# SRAM_MODULE_1_0.net
KiCad netlist of a schematic drawn in EAGLE
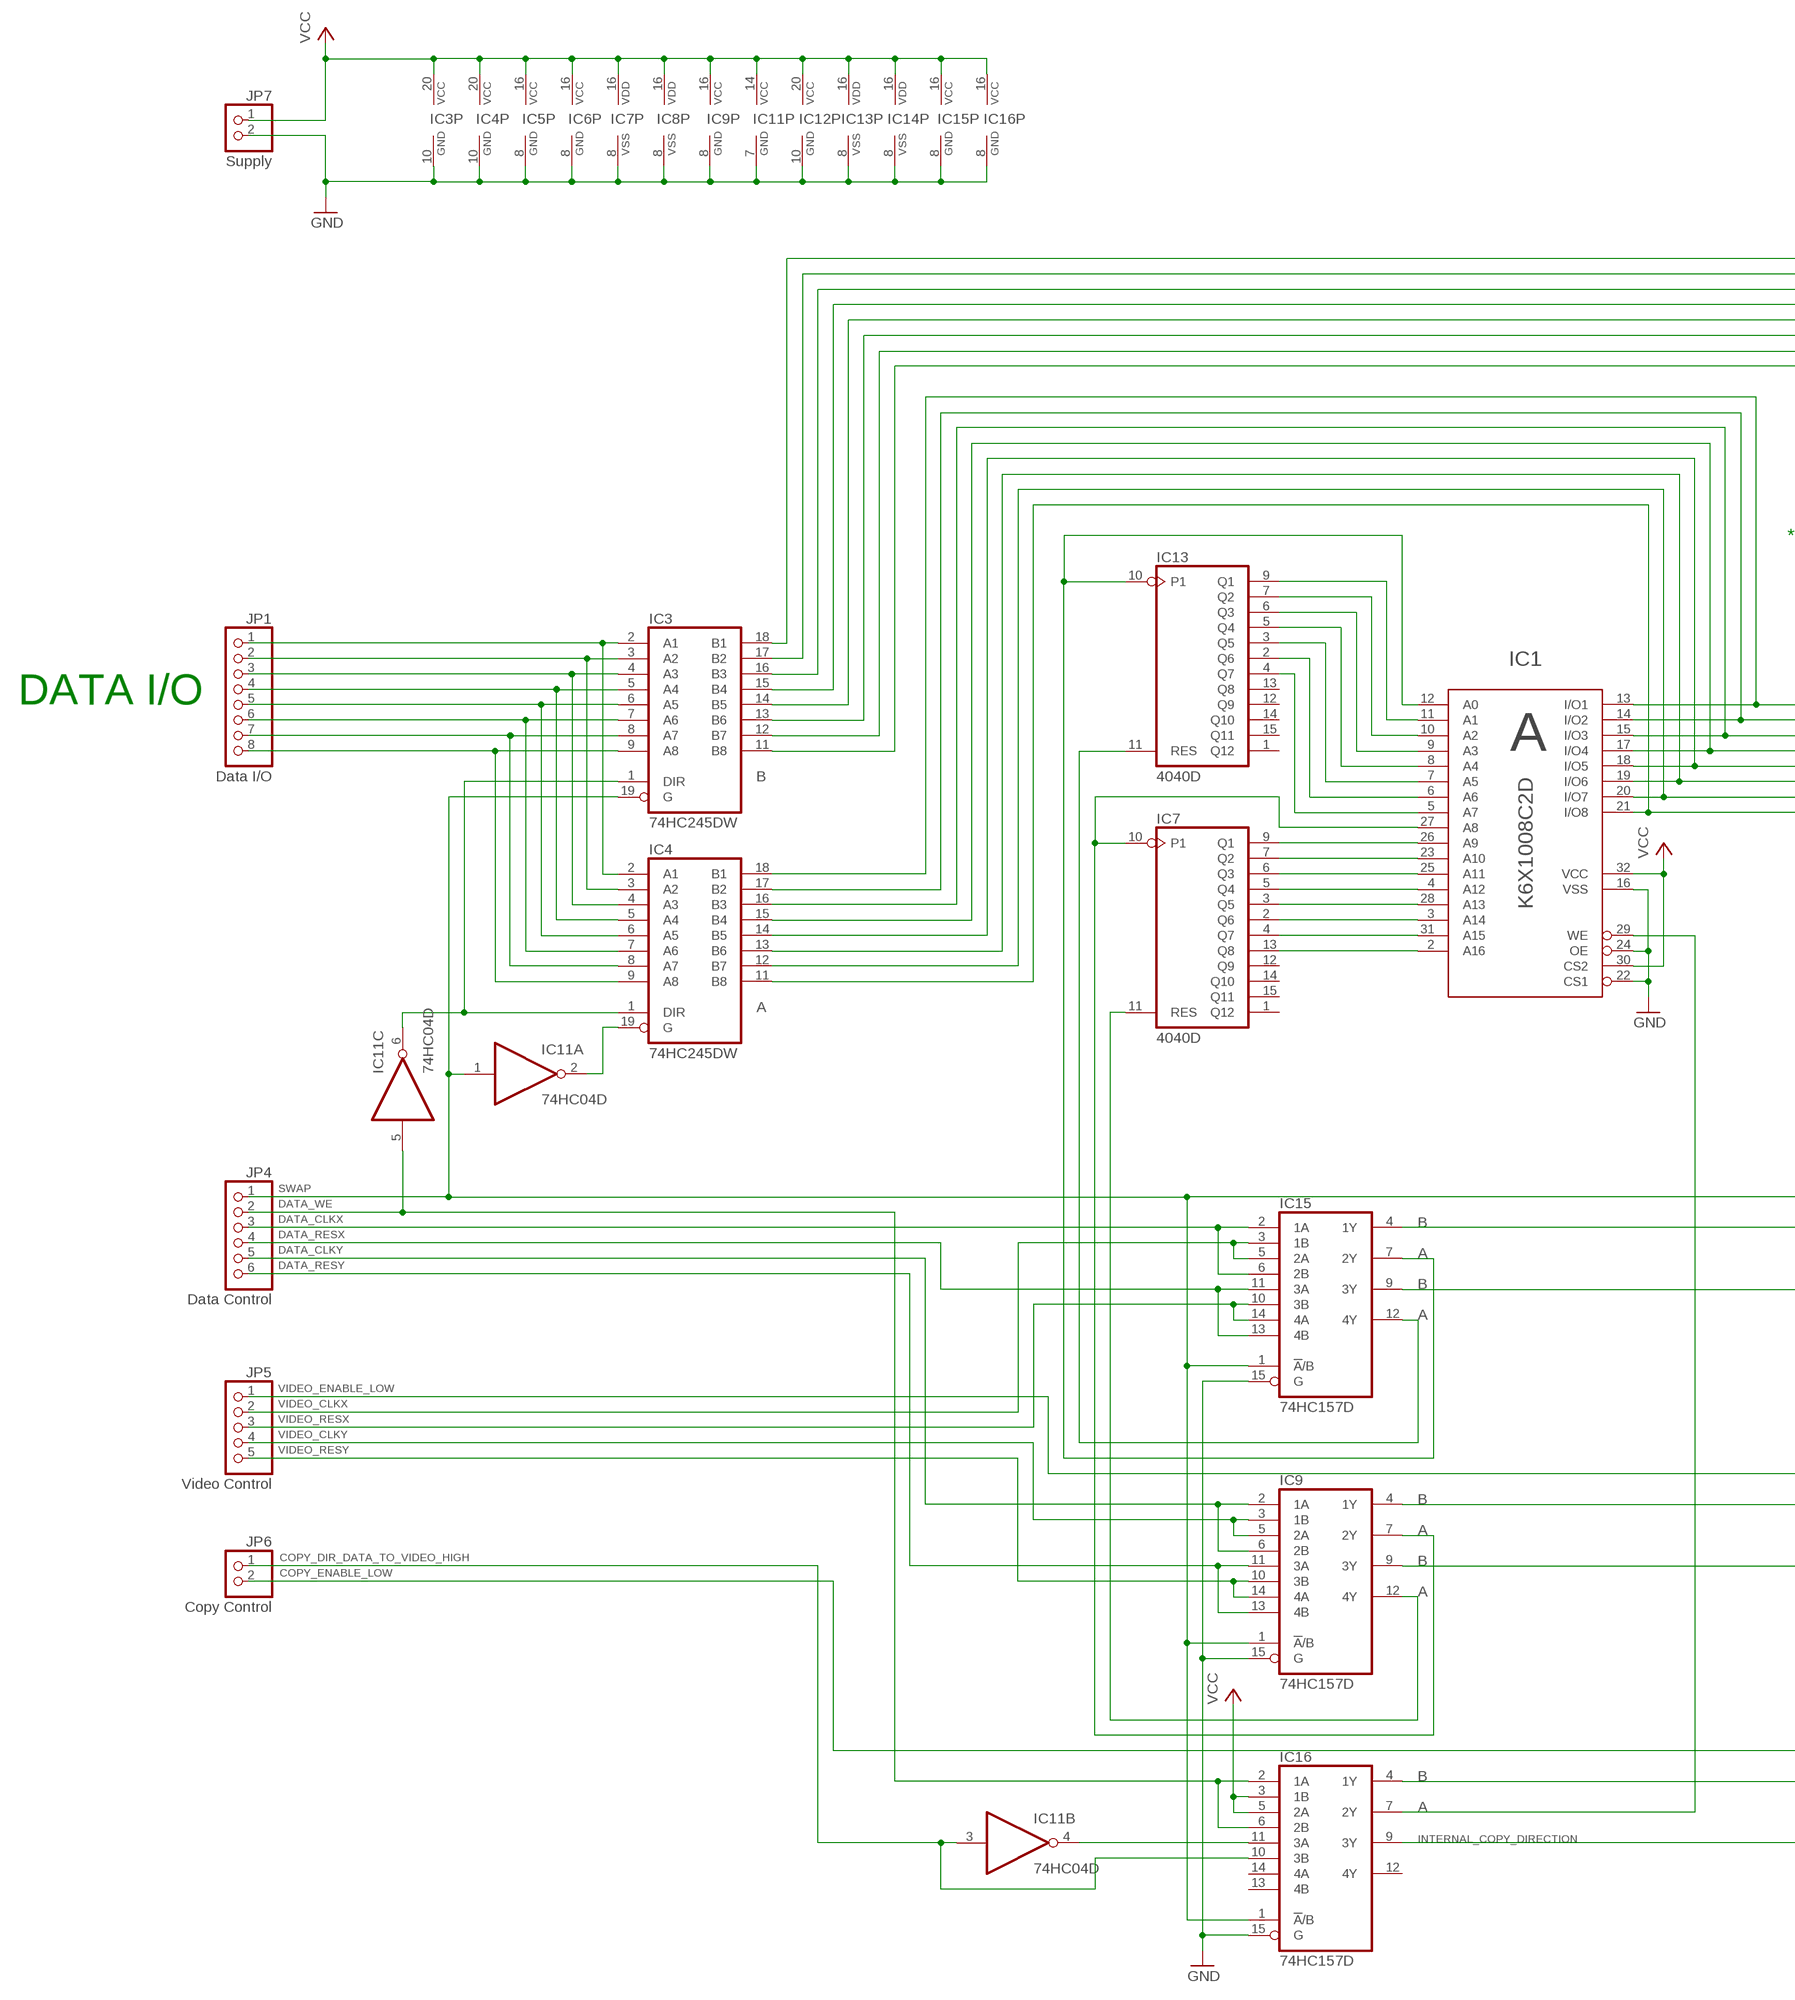
[diagram p0: schematic, sheet 1, part 1 of 2]
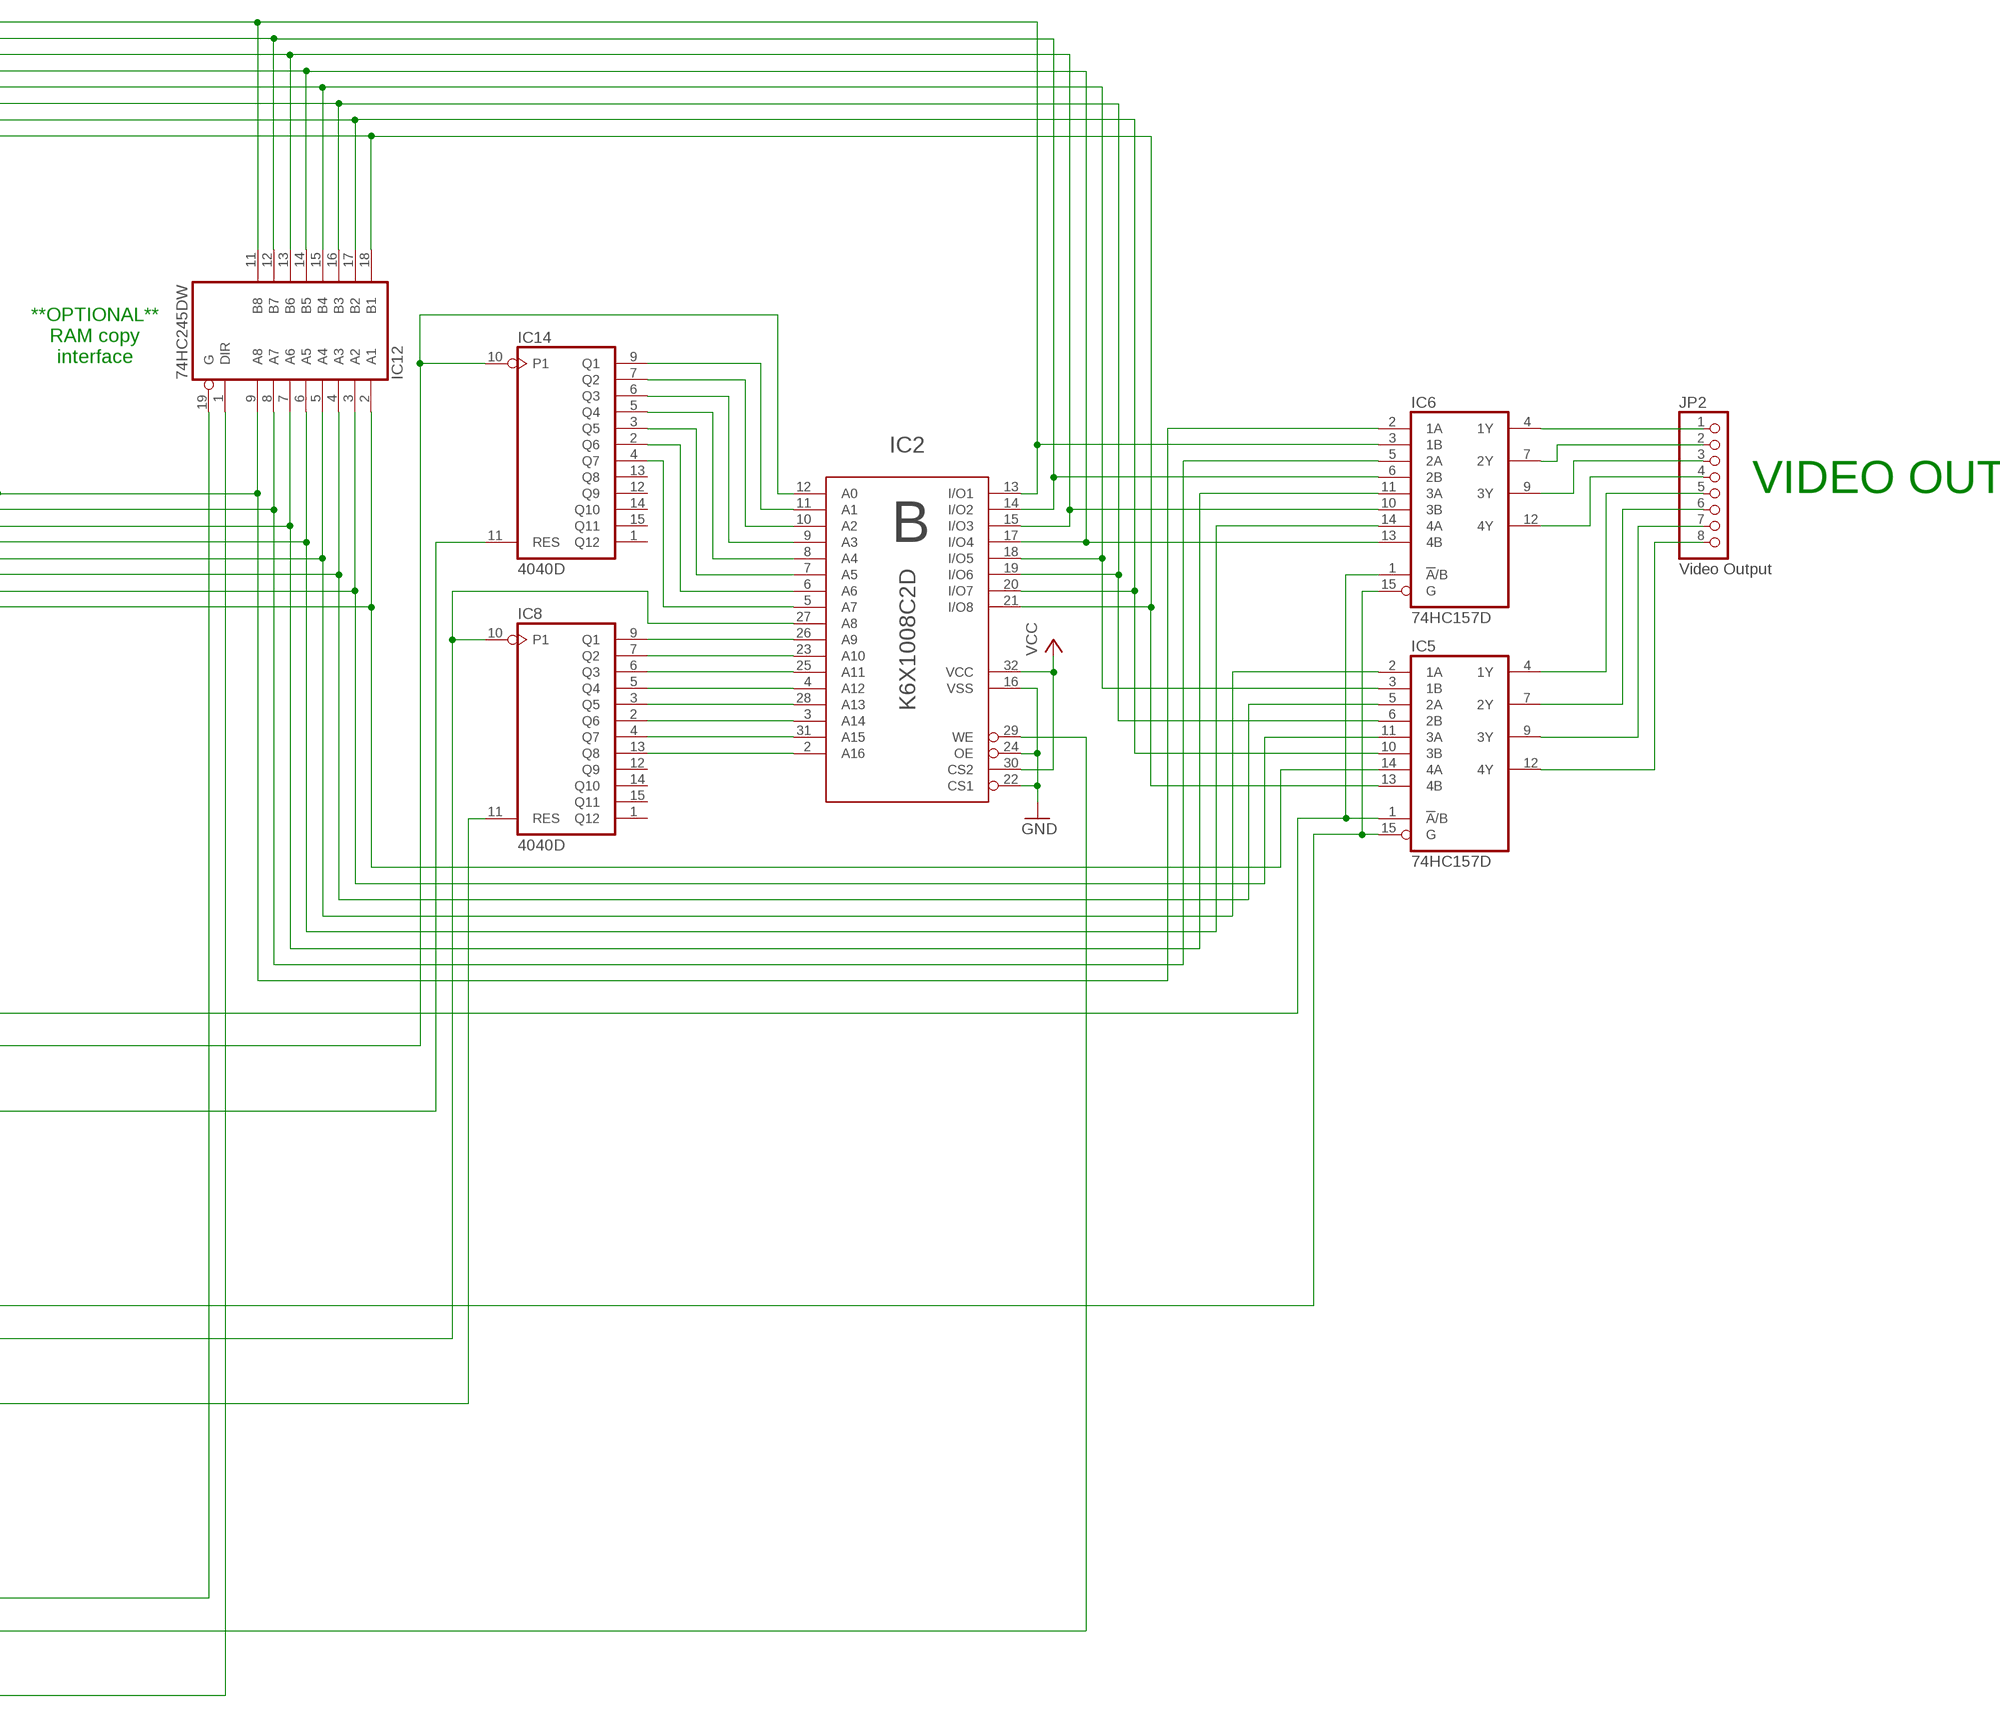
[diagram p1: schematic, sheet 1, part 2 of 2]

(export (version "E")
  (design (tool "Eeschema 10.0.6"))
  (components
    (comp (ref "IC1")
      (value "K6X1008C2D")
      (footprint "eagle-import:SOP32-5")
      (libsource (lib "eagle-import") (part "K6X1008C2D"))
    )
    (comp (ref "IC2")
      (value "K6X1008C2D")
      (footprint "eagle-import:SOP32-5")
      (libsource (lib "eagle-import") (part "K6X1008C2D"))
    )
    (comp (ref "IC3")
      (value "74HC245DW")
      (footprint "eagle-import:SO20W")
      (libsource (lib "eagle-import") (part "74245DWHC"))
    )
    (comp (ref "IC4")
      (value "74HC245DW")
      (footprint "eagle-import:SO20W")
      (libsource (lib "eagle-import") (part "74245DWHC"))
    )
    (comp (ref "IC5")
      (value "74HC157D")
      (footprint "eagle-import:SO16")
      (libsource (lib "eagle-import") (part "74157DHC"))
    )
    (comp (ref "IC6")
      (value "74HC157D")
      (footprint "eagle-import:SO16")
      (libsource (lib "eagle-import") (part "74157DHC"))
    )
    (comp (ref "IC7")
      (value "4040D")
      (footprint "eagle-import:SO16")
      (libsource (lib "eagle-import") (part "4040D"))
    )
    (comp (ref "IC8")
      (value "4040D")
      (footprint "eagle-import:SO16")
      (libsource (lib "eagle-import") (part "4040D"))
    )
    (comp (ref "IC9")
      (value "74HC157D")
      (footprint "eagle-import:SO16")
      (libsource (lib "eagle-import") (part "74157DHC"))
    )
    (comp (ref "IC11")
      (value "74HC04D")
      (footprint "eagle-import:SO14")
      (libsource (lib "eagle-import") (part "7404DHC"))
    )
    (comp (ref "IC12")
      (value "74HC245DW")
      (footprint "eagle-import:SO20W")
      (libsource (lib "eagle-import") (part "74245DWHC"))
    )
    (comp (ref "IC13")
      (value "4040D")
      (footprint "eagle-import:SO16")
      (libsource (lib "eagle-import") (part "4040D"))
    )
    (comp (ref "IC14")
      (value "4040D")
      (footprint "eagle-import:SO16")
      (libsource (lib "eagle-import") (part "4040D"))
    )
    (comp (ref "IC15")
      (value "74HC157D")
      (footprint "eagle-import:SO16")
      (libsource (lib "eagle-import") (part "74157DHC"))
    )
    (comp (ref "IC16")
      (value "74HC157D")
      (footprint "eagle-import:SO16")
      (libsource (lib "eagle-import") (part "74157DHC"))
    )
    (comp (ref "JP1")
      (value "Data I/O")
      (footprint "eagle-import:1X08")
      (libsource (lib "eagle-import") (part "PINHD-1X8"))
    )
    (comp (ref "JP2")
      (value "Video Output")
      (footprint "eagle-import:1X08")
      (libsource (lib "eagle-import") (part "PINHD-1X8"))
    )
    (comp (ref "JP4")
      (value "Data Control")
      (footprint "eagle-import:1X06")
      (libsource (lib "eagle-import") (part "PINHD-1X6"))
    )
    (comp (ref "JP5")
      (value "Video Control")
      (footprint "eagle-import:1X05")
      (libsource (lib "eagle-import") (part "PINHD-1X5"))
    )
    (comp (ref "JP6")
      (value "Copy Control")
      (footprint "eagle-import:1X02")
      (libsource (lib "eagle-import") (part "PINHD-1X2"))
    )
    (comp (ref "JP7")
      (value "Supply")
      (footprint "eagle-import:1X02")
      (libsource (lib "eagle-import") (part "PINHD-1X2"))
    )
  )
  (nets
    (net (code "1") (name "/COPY_DIR_DATA_TO_VIDEO_HIGH") (class "Default")
      (node (ref "IC11") (pin "3") (pinfunction "I_3") (pintype "input"))
      (node (ref "IC16") (pin "10") (pinfunction "3B_10") (pintype "input"))
      (node (ref "JP6") (pin "1") (pinfunction "1_1") (pintype "passive"))
    )
    (net (code "2") (name "/COPY_ENABLE_LOW") (class "Default")
      (node (ref "IC12") (pin "19") (pinfunction "G_19") (pintype "input"))
      (node (ref "JP6") (pin "2") (pinfunction "2_2") (pintype "passive"))
    )
    (net (code "3") (name "/DATA_CLKX") (class "Default")
      (node (ref "IC15") (pin "2") (pinfunction "1A_2") (pintype "input"))
      (node (ref "IC15") (pin "6") (pinfunction "2B_6") (pintype "input"))
      (node (ref "JP4") (pin "3") (pinfunction "3_3") (pintype "passive"))
    )
    (net (code "4") (name "/DATA_CLKY") (class "Default")
      (node (ref "IC9") (pin "2") (pinfunction "1A_2") (pintype "input"))
      (node (ref "IC9") (pin "6") (pinfunction "2B_6") (pintype "input"))
      (node (ref "JP4") (pin "5") (pinfunction "5_5") (pintype "passive"))
    )
    (net (code "5") (name "/DATA_RESX") (class "Default")
      (node (ref "IC15") (pin "11") (pinfunction "3A_11") (pintype "input"))
      (node (ref "IC15") (pin "13") (pinfunction "4B_13") (pintype "input"))
      (node (ref "JP4") (pin "4") (pinfunction "4_4") (pintype "passive"))
    )
    (net (code "6") (name "/DATA_RESY") (class "Default")
      (node (ref "IC9") (pin "11") (pinfunction "3A_11") (pintype "input"))
      (node (ref "IC9") (pin "13") (pinfunction "4B_13") (pintype "input"))
      (node (ref "JP4") (pin "6") (pinfunction "6_6") (pintype "passive"))
    )
    (net (code "7") (name "/DATA_WE") (class "Default")
      (node (ref "IC11") (pin "5") (pinfunction "I_5") (pintype "input"))
      (node (ref "IC16") (pin "2") (pinfunction "1A_2") (pintype "input"))
      (node (ref "IC16") (pin "6") (pinfunction "2B_6") (pintype "input"))
      (node (ref "JP4") (pin "2") (pinfunction "2_2") (pintype "passive"))
    )
    (net (code "8") (name "/INTERNAL_COPY_DIRECTION") (class "Default")
      (node (ref "IC12") (pin "1") (pinfunction "DIR_1") (pintype "input"))
      (node (ref "IC16") (pin "9") (pinfunction "3Y_9") (pintype "output"))
    )
    (net (code "9") (name "/SWAP") (class "Default")
      (node (ref "IC11") (pin "1") (pinfunction "I_1") (pintype "input"))
      (node (ref "IC15") (pin "1") (pinfunction "~{A}/B_1") (pintype "input"))
      (node (ref "IC16") (pin "1") (pinfunction "~{A}/B_1") (pintype "input"))
      (node (ref "IC3") (pin "19") (pinfunction "G_19") (pintype "input"))
      (node (ref "IC5") (pin "1") (pinfunction "~{A}/B_1") (pintype "input"))
      (node (ref "IC6") (pin "1") (pinfunction "~{A}/B_1") (pintype "input"))
      (node (ref "IC9") (pin "1") (pinfunction "~{A}/B_1") (pintype "input"))
      (node (ref "JP4") (pin "1") (pinfunction "1_1") (pintype "passive"))
    )
    (net (code "10") (name "/VIDEO_CLKX") (class "Default")
      (node (ref "IC15") (pin "3") (pinfunction "1B_3") (pintype "input"))
      (node (ref "IC15") (pin "5") (pinfunction "2A_5") (pintype "input"))
      (node (ref "JP5") (pin "2") (pinfunction "2_2") (pintype "passive"))
    )
    (net (code "11") (name "/VIDEO_CLKY") (class "Default")
      (node (ref "IC9") (pin "3") (pinfunction "1B_3") (pintype "input"))
      (node (ref "IC9") (pin "5") (pinfunction "2A_5") (pintype "input"))
      (node (ref "JP5") (pin "4") (pinfunction "4_4") (pintype "passive"))
    )
    (net (code "12") (name "/VIDEO_ENABLE_LOW") (class "Default")
      (node (ref "IC5") (pin "15") (pinfunction "G_15") (pintype "input"))
      (node (ref "IC6") (pin "15") (pinfunction "G_15") (pintype "input"))
      (node (ref "JP5") (pin "1") (pinfunction "1_1") (pintype "passive"))
    )
    (net (code "13") (name "/VIDEO_RESX") (class "Default")
      (node (ref "IC15") (pin "10") (pinfunction "3B_10") (pintype "input"))
      (node (ref "IC15") (pin "14") (pinfunction "4A_14") (pintype "input"))
      (node (ref "JP5") (pin "3") (pinfunction "3_3") (pintype "passive"))
    )
    (net (code "14") (name "/VIDEO_RESY") (class "Default")
      (node (ref "IC9") (pin "10") (pinfunction "3B_10") (pintype "input"))
      (node (ref "IC9") (pin "14") (pinfunction "4A_14") (pintype "input"))
      (node (ref "JP5") (pin "5") (pinfunction "5_5") (pintype "passive"))
    )
    (net (code "15") (name "GND") (class "Default")
      (node (ref "IC1") (pin "16") (pinfunction "VSS_16") (pintype "power_in"))
      (node (ref "IC1") (pin "22") (pinfunction "CS1_22") (pintype "input"))
      (node (ref "IC1") (pin "24") (pinfunction "OE_24") (pintype "input"))
      (node (ref "IC11") (pin "7") (pinfunction "GND_7") (pintype "power_in"))
      (node (ref "IC12") (pin "10") (pinfunction "GND_10") (pintype "power_in"))
      (node (ref "IC13") (pin "8") (pinfunction "VSS_8") (pintype "power_in"))
      (node (ref "IC14") (pin "8") (pinfunction "VSS_8") (pintype "power_in"))
      (node (ref "IC15") (pin "15") (pinfunction "G_15") (pintype "input"))
      (node (ref "IC15") (pin "8") (pinfunction "GND_8") (pintype "power_in"))
      (node (ref "IC16") (pin "15") (pinfunction "G_15") (pintype "input"))
      (node (ref "IC16") (pin "8") (pinfunction "GND_8") (pintype "power_in"))
      (node (ref "IC2") (pin "16") (pinfunction "VSS_16") (pintype "power_in"))
      (node (ref "IC2") (pin "22") (pinfunction "CS1_22") (pintype "input"))
      (node (ref "IC2") (pin "24") (pinfunction "OE_24") (pintype "input"))
      (node (ref "IC3") (pin "10") (pinfunction "GND_10") (pintype "power_in"))
      (node (ref "IC4") (pin "10") (pinfunction "GND_10") (pintype "power_in"))
      (node (ref "IC5") (pin "8") (pinfunction "GND_8") (pintype "power_in"))
      (node (ref "IC6") (pin "8") (pinfunction "GND_8") (pintype "power_in"))
      (node (ref "IC7") (pin "8") (pinfunction "VSS_8") (pintype "power_in"))
      (node (ref "IC8") (pin "8") (pinfunction "VSS_8") (pintype "power_in"))
      (node (ref "IC9") (pin "15") (pinfunction "G_15") (pintype "input"))
      (node (ref "IC9") (pin "8") (pinfunction "GND_8") (pintype "power_in"))
      (node (ref "JP7") (pin "2") (pinfunction "2_2") (pintype "passive"))
    )
    (net (code "16") (name "Net-(IC1-A0)") (class "Default")
      (node (ref "IC1") (pin "12") (pinfunction "A0_12") (pintype "input"))
      (node (ref "IC13") (pin "10") (pinfunction "P1_10") (pintype "input"))
      (node (ref "IC15") (pin "7") (pinfunction "2Y_7") (pintype "output"))
    )
    (net (code "17") (name "Net-(IC1-A1)") (class "Default")
      (node (ref "IC1") (pin "11") (pinfunction "A1_11") (pintype "input"))
      (node (ref "IC13") (pin "9") (pinfunction "Q1_9") (pintype "output"))
    )
    (net (code "18") (name "Net-(IC1-A2)") (class "Default")
      (node (ref "IC1") (pin "10") (pinfunction "A2_10") (pintype "input"))
      (node (ref "IC13") (pin "7") (pinfunction "Q2_7") (pintype "output"))
    )
    (net (code "19") (name "Net-(IC1-A3)") (class "Default")
      (node (ref "IC1") (pin "9") (pinfunction "A3_9") (pintype "input"))
      (node (ref "IC13") (pin "6") (pinfunction "Q3_6") (pintype "output"))
    )
    (net (code "20") (name "Net-(IC1-A4)") (class "Default")
      (node (ref "IC1") (pin "8") (pinfunction "A4_8") (pintype "input"))
      (node (ref "IC13") (pin "5") (pinfunction "Q4_5") (pintype "output"))
    )
    (net (code "21") (name "Net-(IC1-A5)") (class "Default")
      (node (ref "IC1") (pin "7") (pinfunction "A5_7") (pintype "input"))
      (node (ref "IC13") (pin "3") (pinfunction "Q5_3") (pintype "output"))
    )
    (net (code "22") (name "Net-(IC1-A6)") (class "Default")
      (node (ref "IC1") (pin "6") (pinfunction "A6_6") (pintype "input"))
      (node (ref "IC13") (pin "2") (pinfunction "Q6_2") (pintype "output"))
    )
    (net (code "23") (name "Net-(IC1-A7)") (class "Default")
      (node (ref "IC1") (pin "5") (pinfunction "A7_5") (pintype "input"))
      (node (ref "IC13") (pin "4") (pinfunction "Q7_4") (pintype "output"))
    )
    (net (code "24") (name "Net-(IC1-A8)") (class "Default")
      (node (ref "IC1") (pin "27") (pinfunction "A8_27") (pintype "input"))
      (node (ref "IC7") (pin "10") (pinfunction "P1_10") (pintype "input"))
      (node (ref "IC9") (pin "7") (pinfunction "2Y_7") (pintype "output"))
    )
    (net (code "25") (name "Net-(IC1-A9)") (class "Default")
      (node (ref "IC1") (pin "26") (pinfunction "A9_26") (pintype "input"))
      (node (ref "IC7") (pin "9") (pinfunction "Q1_9") (pintype "output"))
    )
    (net (code "26") (name "Net-(IC1-A10)") (class "Default")
      (node (ref "IC1") (pin "23") (pinfunction "A10_23") (pintype "input"))
      (node (ref "IC7") (pin "7") (pinfunction "Q2_7") (pintype "output"))
    )
    (net (code "27") (name "Net-(IC1-A11)") (class "Default")
      (node (ref "IC1") (pin "25") (pinfunction "A11_25") (pintype "input"))
      (node (ref "IC7") (pin "6") (pinfunction "Q3_6") (pintype "output"))
    )
    (net (code "28") (name "Net-(IC1-A12)") (class "Default")
      (node (ref "IC1") (pin "4") (pinfunction "A12_4") (pintype "input"))
      (node (ref "IC7") (pin "5") (pinfunction "Q4_5") (pintype "output"))
    )
    (net (code "29") (name "Net-(IC1-A13)") (class "Default")
      (node (ref "IC1") (pin "28") (pinfunction "A13_28") (pintype "input"))
      (node (ref "IC7") (pin "3") (pinfunction "Q5_3") (pintype "output"))
    )
    (net (code "30") (name "Net-(IC1-A14)") (class "Default")
      (node (ref "IC1") (pin "3") (pinfunction "A14_3") (pintype "input"))
      (node (ref "IC7") (pin "2") (pinfunction "Q6_2") (pintype "output"))
    )
    (net (code "31") (name "Net-(IC1-A15)") (class "Default")
      (node (ref "IC1") (pin "31") (pinfunction "A15_31") (pintype "input"))
      (node (ref "IC7") (pin "4") (pinfunction "Q7_4") (pintype "output"))
    )
    (net (code "32") (name "Net-(IC1-A16)") (class "Default")
      (node (ref "IC1") (pin "2") (pinfunction "A16_2") (pintype "input"))
      (node (ref "IC7") (pin "13") (pinfunction "Q8_13") (pintype "output"))
    )
    (net (code "33") (name "Net-(IC1-I{slash}O1)") (class "Default")
      (node (ref "IC1") (pin "13") (pinfunction "I/O1_13") (pintype "bidirectional"))
      (node (ref "IC12") (pin "9") (pinfunction "A8_9") (pintype "bidirectional"))
      (node (ref "IC4") (pin "18") (pinfunction "B1_18") (pintype "bidirectional"))
      (node (ref "IC6") (pin "2") (pinfunction "1A_2") (pintype "input"))
    )
    (net (code "34") (name "Net-(IC1-I{slash}O2)") (class "Default")
      (node (ref "IC1") (pin "14") (pinfunction "I/O2_14") (pintype "bidirectional"))
      (node (ref "IC12") (pin "8") (pinfunction "A7_8") (pintype "bidirectional"))
      (node (ref "IC4") (pin "17") (pinfunction "B2_17") (pintype "bidirectional"))
      (node (ref "IC6") (pin "5") (pinfunction "2A_5") (pintype "input"))
    )
    (net (code "35") (name "Net-(IC1-I{slash}O3)") (class "Default")
      (node (ref "IC1") (pin "15") (pinfunction "I/O3_15") (pintype "bidirectional"))
      (node (ref "IC12") (pin "7") (pinfunction "A6_7") (pintype "bidirectional"))
      (node (ref "IC4") (pin "16") (pinfunction "B3_16") (pintype "bidirectional"))
      (node (ref "IC6") (pin "11") (pinfunction "3A_11") (pintype "input"))
    )
    (net (code "36") (name "Net-(IC1-I{slash}O4)") (class "Default")
      (node (ref "IC1") (pin "17") (pinfunction "I/O4_17") (pintype "bidirectional"))
      (node (ref "IC12") (pin "6") (pinfunction "A5_6") (pintype "bidirectional"))
      (node (ref "IC4") (pin "15") (pinfunction "B4_15") (pintype "bidirectional"))
      (node (ref "IC6") (pin "14") (pinfunction "4A_14") (pintype "input"))
    )
    (net (code "37") (name "Net-(IC1-I{slash}O5)") (class "Default")
      (node (ref "IC1") (pin "18") (pinfunction "I/O5_18") (pintype "bidirectional"))
      (node (ref "IC12") (pin "5") (pinfunction "A4_5") (pintype "bidirectional"))
      (node (ref "IC4") (pin "14") (pinfunction "B5_14") (pintype "bidirectional"))
      (node (ref "IC5") (pin "2") (pinfunction "1A_2") (pintype "input"))
    )
    (net (code "38") (name "Net-(IC1-I{slash}O6)") (class "Default")
      (node (ref "IC1") (pin "19") (pinfunction "I/O6_19") (pintype "bidirectional"))
      (node (ref "IC12") (pin "4") (pinfunction "A3_4") (pintype "bidirectional"))
      (node (ref "IC4") (pin "13") (pinfunction "B6_13") (pintype "bidirectional"))
      (node (ref "IC5") (pin "5") (pinfunction "2A_5") (pintype "input"))
    )
    (net (code "39") (name "Net-(IC1-I{slash}O7)") (class "Default")
      (node (ref "IC1") (pin "20") (pinfunction "I/O7_20") (pintype "bidirectional"))
      (node (ref "IC12") (pin "3") (pinfunction "A2_3") (pintype "bidirectional"))
      (node (ref "IC4") (pin "12") (pinfunction "B7_12") (pintype "bidirectional"))
      (node (ref "IC5") (pin "11") (pinfunction "3A_11") (pintype "input"))
    )
    (net (code "40") (name "Net-(IC1-I{slash}O8)") (class "Default")
      (node (ref "IC1") (pin "21") (pinfunction "I/O8_21") (pintype "bidirectional"))
      (node (ref "IC12") (pin "2") (pinfunction "A1_2") (pintype "bidirectional"))
      (node (ref "IC4") (pin "11") (pinfunction "B8_11") (pintype "bidirectional"))
      (node (ref "IC5") (pin "14") (pinfunction "4A_14") (pintype "input"))
    )
    (net (code "41") (name "Net-(IC1-WE)") (class "Default")
      (node (ref "IC1") (pin "29") (pinfunction "WE_29") (pintype "input"))
      (node (ref "IC16") (pin "7") (pinfunction "2Y_7") (pintype "output"))
    )
    (net (code "42") (name "Net-(IC2-A8)") (class "Default")
      (node (ref "IC2") (pin "27") (pinfunction "A8_27") (pintype "input"))
      (node (ref "IC8") (pin "10") (pinfunction "P1_10") (pintype "input"))
      (node (ref "IC9") (pin "4") (pinfunction "1Y_4") (pintype "output"))
    )
    (net (code "43") (name "Net-(IC2-A9)") (class "Default")
      (node (ref "IC2") (pin "26") (pinfunction "A9_26") (pintype "input"))
      (node (ref "IC8") (pin "9") (pinfunction "Q1_9") (pintype "output"))
    )
    (net (code "44") (name "Net-(IC2-A10)") (class "Default")
      (node (ref "IC2") (pin "23") (pinfunction "A10_23") (pintype "input"))
      (node (ref "IC8") (pin "7") (pinfunction "Q2_7") (pintype "output"))
    )
    (net (code "45") (name "Net-(IC2-A11)") (class "Default")
      (node (ref "IC2") (pin "25") (pinfunction "A11_25") (pintype "input"))
      (node (ref "IC8") (pin "6") (pinfunction "Q3_6") (pintype "output"))
    )
    (net (code "46") (name "Net-(IC2-A12)") (class "Default")
      (node (ref "IC2") (pin "4") (pinfunction "A12_4") (pintype "input"))
      (node (ref "IC8") (pin "5") (pinfunction "Q4_5") (pintype "output"))
    )
    (net (code "47") (name "Net-(IC2-A13)") (class "Default")
      (node (ref "IC2") (pin "28") (pinfunction "A13_28") (pintype "input"))
      (node (ref "IC8") (pin "3") (pinfunction "Q5_3") (pintype "output"))
    )
    (net (code "48") (name "Net-(IC2-A14)") (class "Default")
      (node (ref "IC2") (pin "3") (pinfunction "A14_3") (pintype "input"))
      (node (ref "IC8") (pin "2") (pinfunction "Q6_2") (pintype "output"))
    )
    (net (code "49") (name "Net-(IC2-A15)") (class "Default")
      (node (ref "IC2") (pin "31") (pinfunction "A15_31") (pintype "input"))
      (node (ref "IC8") (pin "4") (pinfunction "Q7_4") (pintype "output"))
    )
    (net (code "50") (name "Net-(IC2-A16)") (class "Default")
      (node (ref "IC2") (pin "2") (pinfunction "A16_2") (pintype "input"))
      (node (ref "IC8") (pin "13") (pinfunction "Q8_13") (pintype "output"))
    )
    (net (code "51") (name "Net-(IC3A-A1)") (class "Default")
      (node (ref "IC3") (pin "2") (pinfunction "A1_2") (pintype "bidirectional"))
      (node (ref "IC4") (pin "2") (pinfunction "A1_2") (pintype "bidirectional"))
      (node (ref "JP1") (pin "1") (pinfunction "1_1") (pintype "passive"))
    )
    (net (code "52") (name "Net-(IC3A-A2)") (class "Default")
      (node (ref "IC3") (pin "3") (pinfunction "A2_3") (pintype "bidirectional"))
      (node (ref "IC4") (pin "3") (pinfunction "A2_3") (pintype "bidirectional"))
      (node (ref "JP1") (pin "2") (pinfunction "2_2") (pintype "passive"))
    )
    (net (code "53") (name "Net-(IC3A-A3)") (class "Default")
      (node (ref "IC3") (pin "4") (pinfunction "A3_4") (pintype "bidirectional"))
      (node (ref "IC4") (pin "4") (pinfunction "A3_4") (pintype "bidirectional"))
      (node (ref "JP1") (pin "3") (pinfunction "3_3") (pintype "passive"))
    )
    (net (code "54") (name "Net-(IC3A-A4)") (class "Default")
      (node (ref "IC3") (pin "5") (pinfunction "A4_5") (pintype "bidirectional"))
      (node (ref "IC4") (pin "5") (pinfunction "A4_5") (pintype "bidirectional"))
      (node (ref "JP1") (pin "4") (pinfunction "4_4") (pintype "passive"))
    )
    (net (code "55") (name "Net-(IC3A-A5)") (class "Default")
      (node (ref "IC3") (pin "6") (pinfunction "A5_6") (pintype "bidirectional"))
      (node (ref "IC4") (pin "6") (pinfunction "A5_6") (pintype "bidirectional"))
      (node (ref "JP1") (pin "5") (pinfunction "5_5") (pintype "passive"))
    )
    (net (code "56") (name "Net-(IC3A-A6)") (class "Default")
      (node (ref "IC3") (pin "7") (pinfunction "A6_7") (pintype "bidirectional"))
      (node (ref "IC4") (pin "7") (pinfunction "A6_7") (pintype "bidirectional"))
      (node (ref "JP1") (pin "6") (pinfunction "6_6") (pintype "passive"))
    )
    (net (code "57") (name "Net-(IC3A-A7)") (class "Default")
      (node (ref "IC3") (pin "8") (pinfunction "A7_8") (pintype "bidirectional"))
      (node (ref "IC4") (pin "8") (pinfunction "A7_8") (pintype "bidirectional"))
      (node (ref "JP1") (pin "7") (pinfunction "7_7") (pintype "passive"))
    )
    (net (code "58") (name "Net-(IC3A-A8)") (class "Default")
      (node (ref "IC3") (pin "9") (pinfunction "A8_9") (pintype "bidirectional"))
      (node (ref "IC4") (pin "9") (pinfunction "A8_9") (pintype "bidirectional"))
      (node (ref "JP1") (pin "8") (pinfunction "8_8") (pintype "passive"))
    )
    (net (code "59") (name "Net-(IC5A-1Y)") (class "Default")
      (node (ref "IC5") (pin "4") (pinfunction "1Y_4") (pintype "output"))
      (node (ref "JP2") (pin "5") (pinfunction "5_5") (pintype "passive"))
    )
    (net (code "60") (name "Net-(IC5A-2Y)") (class "Default")
      (node (ref "IC5") (pin "7") (pinfunction "2Y_7") (pintype "output"))
      (node (ref "JP2") (pin "6") (pinfunction "6_6") (pintype "passive"))
    )
    (net (code "61") (name "Net-(IC5A-3Y)") (class "Default")
      (node (ref "IC5") (pin "9") (pinfunction "3Y_9") (pintype "output"))
      (node (ref "JP2") (pin "7") (pinfunction "7_7") (pintype "passive"))
    )
    (net (code "62") (name "Net-(IC5A-4Y)") (class "Default")
      (node (ref "IC5") (pin "12") (pinfunction "4Y_12") (pintype "output"))
      (node (ref "JP2") (pin "8") (pinfunction "8_8") (pintype "passive"))
    )
    (net (code "63") (name "Net-(IC6A-1Y)") (class "Default")
      (node (ref "IC6") (pin "4") (pinfunction "1Y_4") (pintype "output"))
      (node (ref "JP2") (pin "1") (pinfunction "1_1") (pintype "passive"))
    )
    (net (code "64") (name "Net-(IC6A-2Y)") (class "Default")
      (node (ref "IC6") (pin "7") (pinfunction "2Y_7") (pintype "output"))
      (node (ref "JP2") (pin "2") (pinfunction "2_2") (pintype "passive"))
    )
    (net (code "65") (name "Net-(IC6A-3Y)") (class "Default")
      (node (ref "IC6") (pin "9") (pinfunction "3Y_9") (pintype "output"))
      (node (ref "JP2") (pin "3") (pinfunction "3_3") (pintype "passive"))
    )
    (net (code "66") (name "Net-(IC6A-4Y)") (class "Default")
      (node (ref "IC6") (pin "12") (pinfunction "4Y_12") (pintype "output"))
      (node (ref "JP2") (pin "4") (pinfunction "4_4") (pintype "passive"))
    )
    (net (code "67") (name "Net-(IC7A-RES)") (class "Default")
      (node (ref "IC7") (pin "11") (pinfunction "RES_11") (pintype "input"))
      (node (ref "IC9") (pin "12") (pinfunction "4Y_12") (pintype "output"))
    )
    (net (code "68") (name "Net-(IC8A-RES)") (class "Default")
      (node (ref "IC8") (pin "11") (pinfunction "RES_11") (pintype "input"))
      (node (ref "IC9") (pin "9") (pinfunction "3Y_9") (pintype "output"))
    )
    (net (code "69") (name "Net-(IC11A-O)") (class "Default")
      (node (ref "IC11") (pin "2") (pinfunction "O_2") (pintype "output"))
      (node (ref "IC4") (pin "19") (pinfunction "G_19") (pintype "input"))
    )
    (net (code "70") (name "Net-(IC11B-O)") (class "Default")
      (node (ref "IC11") (pin "4") (pinfunction "O_4") (pintype "output"))
      (node (ref "IC16") (pin "11") (pinfunction "3A_11") (pintype "input"))
    )
    (net (code "71") (name "Net-(IC11C-O)") (class "Default")
      (node (ref "IC11") (pin "6") (pinfunction "O_6") (pintype "output"))
      (node (ref "IC3") (pin "1") (pinfunction "DIR_1") (pintype "input"))
      (node (ref "IC4") (pin "1") (pinfunction "DIR_1") (pintype "input"))
    )
    (net (code "72") (name "Net-(IC12A-B1)") (class "Default")
      (node (ref "IC12") (pin "18") (pinfunction "B1_18") (pintype "bidirectional"))
      (node (ref "IC2") (pin "21") (pinfunction "I/O8_21") (pintype "bidirectional"))
      (node (ref "IC3") (pin "11") (pinfunction "B8_11") (pintype "bidirectional"))
      (node (ref "IC5") (pin "13") (pinfunction "4B_13") (pintype "input"))
    )
    (net (code "73") (name "Net-(IC12A-B2)") (class "Default")
      (node (ref "IC12") (pin "17") (pinfunction "B2_17") (pintype "bidirectional"))
      (node (ref "IC2") (pin "20") (pinfunction "I/O7_20") (pintype "bidirectional"))
      (node (ref "IC3") (pin "12") (pinfunction "B7_12") (pintype "bidirectional"))
      (node (ref "IC5") (pin "10") (pinfunction "3B_10") (pintype "input"))
    )
    (net (code "74") (name "Net-(IC12A-B3)") (class "Default")
      (node (ref "IC12") (pin "16") (pinfunction "B3_16") (pintype "bidirectional"))
      (node (ref "IC2") (pin "19") (pinfunction "I/O6_19") (pintype "bidirectional"))
      (node (ref "IC3") (pin "13") (pinfunction "B6_13") (pintype "bidirectional"))
      (node (ref "IC5") (pin "6") (pinfunction "2B_6") (pintype "input"))
    )
    (net (code "75") (name "Net-(IC12A-B4)") (class "Default")
      (node (ref "IC12") (pin "15") (pinfunction "B4_15") (pintype "bidirectional"))
      (node (ref "IC2") (pin "18") (pinfunction "I/O5_18") (pintype "bidirectional"))
      (node (ref "IC3") (pin "14") (pinfunction "B5_14") (pintype "bidirectional"))
      (node (ref "IC5") (pin "3") (pinfunction "1B_3") (pintype "input"))
    )
    (net (code "76") (name "Net-(IC12A-B5)") (class "Default")
      (node (ref "IC12") (pin "14") (pinfunction "B5_14") (pintype "bidirectional"))
      (node (ref "IC2") (pin "17") (pinfunction "I/O4_17") (pintype "bidirectional"))
      (node (ref "IC3") (pin "15") (pinfunction "B4_15") (pintype "bidirectional"))
      (node (ref "IC6") (pin "13") (pinfunction "4B_13") (pintype "input"))
    )
    (net (code "77") (name "Net-(IC12A-B6)") (class "Default")
      (node (ref "IC12") (pin "13") (pinfunction "B6_13") (pintype "bidirectional"))
      (node (ref "IC2") (pin "15") (pinfunction "I/O3_15") (pintype "bidirectional"))
      (node (ref "IC3") (pin "16") (pinfunction "B3_16") (pintype "bidirectional"))
      (node (ref "IC6") (pin "10") (pinfunction "3B_10") (pintype "input"))
    )
    (net (code "78") (name "Net-(IC12A-B7)") (class "Default")
      (node (ref "IC12") (pin "12") (pinfunction "B7_12") (pintype "bidirectional"))
      (node (ref "IC2") (pin "14") (pinfunction "I/O2_14") (pintype "bidirectional"))
      (node (ref "IC3") (pin "17") (pinfunction "B2_17") (pintype "bidirectional"))
      (node (ref "IC6") (pin "6") (pinfunction "2B_6") (pintype "input"))
    )
    (net (code "79") (name "Net-(IC12A-B8)") (class "Default")
      (node (ref "IC12") (pin "11") (pinfunction "B8_11") (pintype "bidirectional"))
      (node (ref "IC2") (pin "13") (pinfunction "I/O1_13") (pintype "bidirectional"))
      (node (ref "IC3") (pin "18") (pinfunction "B1_18") (pintype "bidirectional"))
      (node (ref "IC6") (pin "3") (pinfunction "1B_3") (pintype "input"))
    )
    (net (code "80") (name "Net-(IC13A-RES)") (class "Default")
      (node (ref "IC13") (pin "11") (pinfunction "RES_11") (pintype "input"))
      (node (ref "IC15") (pin "12") (pinfunction "4Y_12") (pintype "output"))
    )
    (net (code "81") (name "Net-(IC14A-P1)") (class "Default")
      (node (ref "IC14") (pin "10") (pinfunction "P1_10") (pintype "input"))
      (node (ref "IC15") (pin "4") (pinfunction "1Y_4") (pintype "output"))
      (node (ref "IC2") (pin "12") (pinfunction "A0_12") (pintype "input"))
    )
    (net (code "82") (name "Net-(IC14A-Q1)") (class "Default")
      (node (ref "IC14") (pin "9") (pinfunction "Q1_9") (pintype "output"))
      (node (ref "IC2") (pin "11") (pinfunction "A1_11") (pintype "input"))
    )
    (net (code "83") (name "Net-(IC14A-Q2)") (class "Default")
      (node (ref "IC14") (pin "7") (pinfunction "Q2_7") (pintype "output"))
      (node (ref "IC2") (pin "10") (pinfunction "A2_10") (pintype "input"))
    )
    (net (code "84") (name "Net-(IC14A-Q3)") (class "Default")
      (node (ref "IC14") (pin "6") (pinfunction "Q3_6") (pintype "output"))
      (node (ref "IC2") (pin "9") (pinfunction "A3_9") (pintype "input"))
    )
    (net (code "85") (name "Net-(IC14A-Q4)") (class "Default")
      (node (ref "IC14") (pin "5") (pinfunction "Q4_5") (pintype "output"))
      (node (ref "IC2") (pin "8") (pinfunction "A4_8") (pintype "input"))
    )
    (net (code "86") (name "Net-(IC14A-Q5)") (class "Default")
      (node (ref "IC14") (pin "3") (pinfunction "Q5_3") (pintype "output"))
      (node (ref "IC2") (pin "7") (pinfunction "A5_7") (pintype "input"))
    )
    (net (code "87") (name "Net-(IC14A-Q6)") (class "Default")
      (node (ref "IC14") (pin "2") (pinfunction "Q6_2") (pintype "output"))
      (node (ref "IC2") (pin "6") (pinfunction "A6_6") (pintype "input"))
    )
    (net (code "88") (name "Net-(IC14A-Q7)") (class "Default")
      (node (ref "IC14") (pin "4") (pinfunction "Q7_4") (pintype "output"))
      (node (ref "IC2") (pin "5") (pinfunction "A7_5") (pintype "input"))
    )
    (net (code "89") (name "Net-(IC14A-RES)") (class "Default")
      (node (ref "IC14") (pin "11") (pinfunction "RES_11") (pintype "input"))
      (node (ref "IC15") (pin "9") (pinfunction "3Y_9") (pintype "output"))
    )
    (net (code "90") (name "Net-(IC16A-1Y)") (class "Default")
      (node (ref "IC16") (pin "4") (pinfunction "1Y_4") (pintype "output"))
      (node (ref "IC2") (pin "29") (pinfunction "WE_29") (pintype "input"))
    )
    (net (code "91") (name "VCC") (class "Default")
      (node (ref "IC1") (pin "30") (pinfunction "CS2_30") (pintype "input"))
      (node (ref "IC1") (pin "32") (pinfunction "VCC_32") (pintype "power_in"))
      (node (ref "IC11") (pin "14") (pinfunction "VCC_14") (pintype "power_in"))
      (node (ref "IC12") (pin "20") (pinfunction "VCC_20") (pintype "power_in"))
      (node (ref "IC13") (pin "16") (pinfunction "VDD_16") (pintype "power_in"))
      (node (ref "IC14") (pin "16") (pinfunction "VDD_16") (pintype "power_in"))
      (node (ref "IC15") (pin "16") (pinfunction "VCC_16") (pintype "power_in"))
      (node (ref "IC16") (pin "16") (pinfunction "VCC_16") (pintype "power_in"))
      (node (ref "IC16") (pin "3") (pinfunction "1B_3") (pintype "input"))
      (node (ref "IC16") (pin "5") (pinfunction "2A_5") (pintype "input"))
      (node (ref "IC2") (pin "30") (pinfunction "CS2_30") (pintype "input"))
      (node (ref "IC2") (pin "32") (pinfunction "VCC_32") (pintype "power_in"))
      (node (ref "IC3") (pin "20") (pinfunction "VCC_20") (pintype "power_in"))
      (node (ref "IC4") (pin "20") (pinfunction "VCC_20") (pintype "power_in"))
      (node (ref "IC5") (pin "16") (pinfunction "VCC_16") (pintype "power_in"))
      (node (ref "IC6") (pin "16") (pinfunction "VCC_16") (pintype "power_in"))
      (node (ref "IC7") (pin "16") (pinfunction "VDD_16") (pintype "power_in"))
      (node (ref "IC8") (pin "16") (pinfunction "VDD_16") (pintype "power_in"))
      (node (ref "IC9") (pin "16") (pinfunction "VCC_16") (pintype "power_in"))
      (node (ref "JP7") (pin "1") (pinfunction "1_1") (pintype "passive"))
    )
    (net (code "92") (name "unconnected-(IC7A-Q9-Pad12)") (class "Default")
      (node (ref "IC7") (pin "12") (pinfunction "Q9_12") (pintype "output"))
    )
    (net (code "93") (name "unconnected-(IC7A-Q10-Pad14)") (class "Default")
      (node (ref "IC7") (pin "14") (pinfunction "Q10_14") (pintype "output"))
    )
    (net (code "94") (name "unconnected-(IC7A-Q11-Pad15)") (class "Default")
      (node (ref "IC7") (pin "15") (pinfunction "Q11_15") (pintype "output"))
    )
    (net (code "95") (name "unconnected-(IC7A-Q12-Pad1)") (class "Default")
      (node (ref "IC7") (pin "1") (pinfunction "Q12_1") (pintype "output"))
    )
    (net (code "96") (name "unconnected-(IC8A-Q9-Pad12)") (class "Default")
      (node (ref "IC8") (pin "12") (pinfunction "Q9_12") (pintype "output"))
    )
    (net (code "97") (name "unconnected-(IC8A-Q10-Pad14)") (class "Default")
      (node (ref "IC8") (pin "14") (pinfunction "Q10_14") (pintype "output"))
    )
    (net (code "98") (name "unconnected-(IC8A-Q11-Pad15)") (class "Default")
      (node (ref "IC8") (pin "15") (pinfunction "Q11_15") (pintype "output"))
    )
    (net (code "99") (name "unconnected-(IC8A-Q12-Pad1)") (class "Default")
      (node (ref "IC8") (pin "1") (pinfunction "Q12_1") (pintype "output"))
    )
    (net (code "100") (name "unconnected-(IC13A-Q8-Pad13)") (class "Default")
      (node (ref "IC13") (pin "13") (pinfunction "Q8_13") (pintype "output"))
    )
    (net (code "101") (name "unconnected-(IC13A-Q9-Pad12)") (class "Default")
      (node (ref "IC13") (pin "12") (pinfunction "Q9_12") (pintype "output"))
    )
    (net (code "102") (name "unconnected-(IC13A-Q10-Pad14)") (class "Default")
      (node (ref "IC13") (pin "14") (pinfunction "Q10_14") (pintype "output"))
    )
    (net (code "103") (name "unconnected-(IC13A-Q11-Pad15)") (class "Default")
      (node (ref "IC13") (pin "15") (pinfunction "Q11_15") (pintype "output"))
    )
    (net (code "104") (name "unconnected-(IC13A-Q12-Pad1)") (class "Default")
      (node (ref "IC13") (pin "1") (pinfunction "Q12_1") (pintype "output"))
    )
    (net (code "105") (name "unconnected-(IC14A-Q8-Pad13)") (class "Default")
      (node (ref "IC14") (pin "13") (pinfunction "Q8_13") (pintype "output"))
    )
    (net (code "106") (name "unconnected-(IC14A-Q9-Pad12)") (class "Default")
      (node (ref "IC14") (pin "12") (pinfunction "Q9_12") (pintype "output"))
    )
    (net (code "107") (name "unconnected-(IC14A-Q10-Pad14)") (class "Default")
      (node (ref "IC14") (pin "14") (pinfunction "Q10_14") (pintype "output"))
    )
    (net (code "108") (name "unconnected-(IC14A-Q11-Pad15)") (class "Default")
      (node (ref "IC14") (pin "15") (pinfunction "Q11_15") (pintype "output"))
    )
    (net (code "109") (name "unconnected-(IC14A-Q12-Pad1)") (class "Default")
      (node (ref "IC14") (pin "1") (pinfunction "Q12_1") (pintype "output"))
    )
    (net (code "110") (name "unconnected-(IC16A-4A-Pad14)") (class "Default")
      (node (ref "IC16") (pin "14") (pinfunction "4A_14") (pintype "input"))
    )
    (net (code "111") (name "unconnected-(IC16A-4B-Pad13)") (class "Default")
      (node (ref "IC16") (pin "13") (pinfunction "4B_13") (pintype "input"))
    )
    (net (code "112") (name "unconnected-(IC16A-4Y-Pad12)") (class "Default")
      (node (ref "IC16") (pin "12") (pinfunction "4Y_12") (pintype "output"))
    )
  )
)
